# Poti.net
KiCad netlist of a schematic drawn in EAGLE
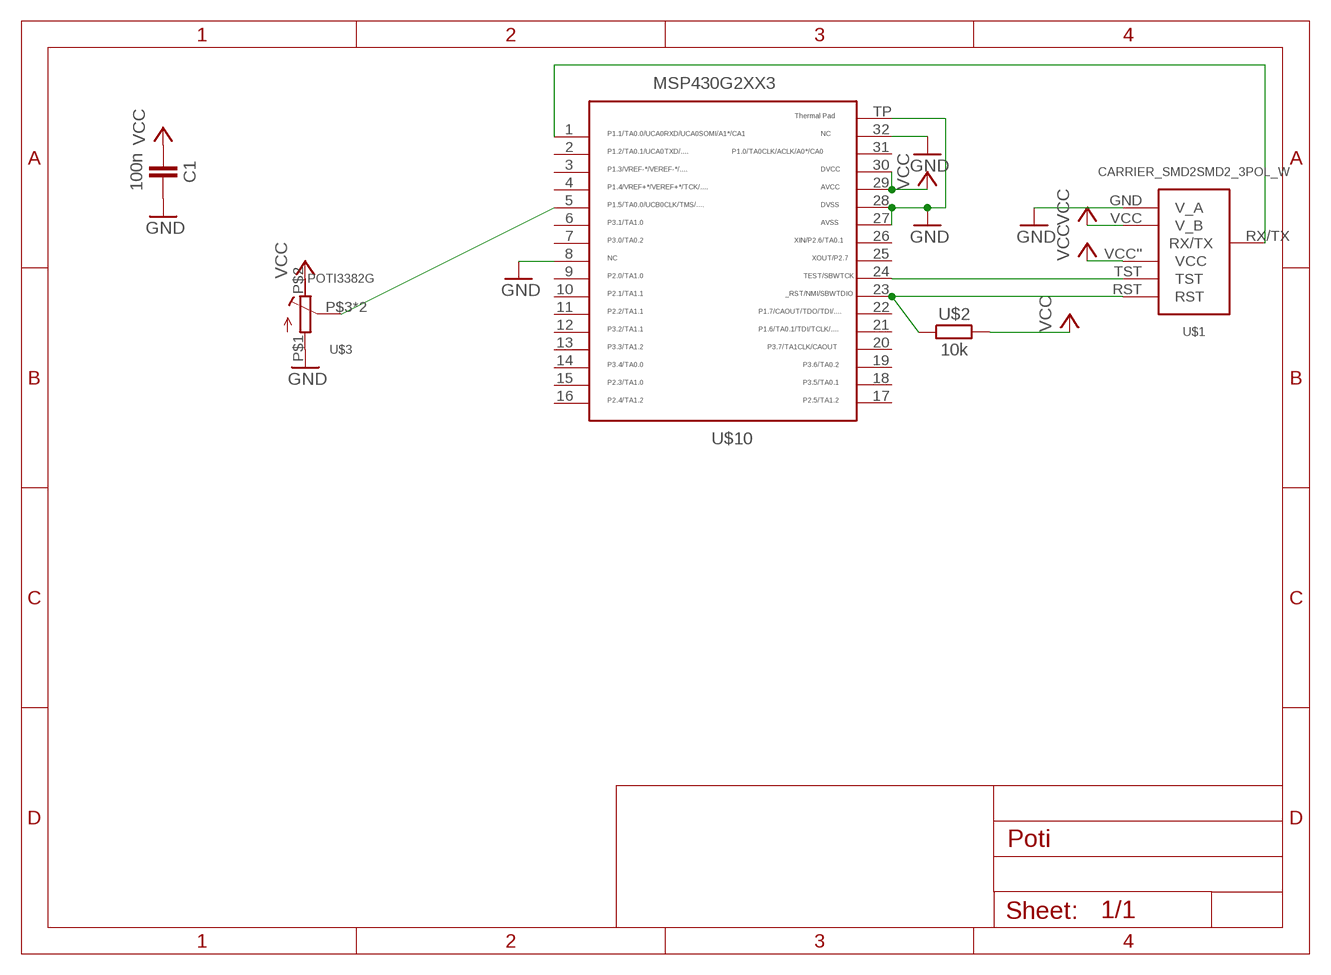
[diagram p0: schematic, sheet 1]

(export (version "E")
  (design (tool "Eeschema 10.0.6"))
  (components
    (comp (ref "C1")
      (value "100n")
      (footprint "eagle-import:603")
      (libsource (lib "eagle-import") (part "CAPACITOR"))
    )
    (comp (ref "U$1")
      (value "CARRIER_SMD2SMD2_3POL_W")
      (footprint "eagle-import:CARRIER_SMD2_WIDE_3POL")
      (libsource (lib "eagle-import") (part "CARRIER_SMD2SMD2_3POL_W"))
    )
    (comp (ref "U$2")
      (value "10k")
      (footprint "eagle-import:603")
      (libsource (lib "eagle-import") (part "RESISTOR0603"))
    )
    (comp (ref "U$3")
      (value "POTI3382G")
      (footprint "eagle-import:3382G")
      (libsource (lib "eagle-import") (part "POTI3382G"))
    )
    (comp (ref "U$10")
      (value "MSP430G2553")
      (footprint "eagle-import:QFN32")
      (libsource (lib "eagle-import") (part "MSP430G2553"))
    )
  )
  (nets
    (net (code "1") (name "GND") (class "Default")
      (node (ref "C1") (pin "2") (pinfunction "2_2") (pintype "passive"))
      (node (ref "U$1") (pin "GND") (pinfunction "V_A_GND") (pintype "bidirectional"))
      (node (ref "U$10") (pin "27") (pinfunction "27_27") (pintype "bidirectional"))
      (node (ref "U$10") (pin "28") (pinfunction "28_28") (pintype "bidirectional"))
      (node (ref "U$10") (pin "32") (pinfunction "32_32") (pintype "bidirectional"))
      (node (ref "U$10") (pin "8") (pinfunction "8_8") (pintype "bidirectional"))
      (node (ref "U$10") (pin "TP") (pinfunction "TP_TP") (pintype "bidirectional"))
      (node (ref "U$3") (pin "P$1") (pinfunction "A_P$1") (pintype "passive"))
    )
    (net (code "2") (name "Net-(U$1-PadRST)") (class "Default")
      (node (ref "U$1") (pin "RST") (pinfunction "RST_RST") (pintype "bidirectional"))
      (node (ref "U$10") (pin "23") (pinfunction "23_23") (pintype "bidirectional"))
      (node (ref "U$2") (pin "1") (pinfunction "1_1") (pintype "passive"))
    )
    (net (code "3") (name "Net-(U$1-PadRX{slash}TX)") (class "Default")
      (node (ref "U$1") (pin "RX/TX") (pinfunction "RX/TX_RX/TX") (pintype "bidirectional"))
      (node (ref "U$10") (pin "1") (pinfunction "1_1") (pintype "bidirectional"))
    )
    (net (code "4") (name "Net-(U$1-PadTST)") (class "Default")
      (node (ref "U$1") (pin "TST") (pinfunction "TST_TST") (pintype "bidirectional"))
      (node (ref "U$10") (pin "24") (pinfunction "24_24") (pintype "bidirectional"))
    )
    (net (code "5") (name "Net-(U$10-Pad5)") (class "Default")
      (node (ref "U$10") (pin "5") (pinfunction "5_5") (pintype "bidirectional"))
      (node (ref "U$3") (pin "P$3") (pinfunction "S_P$3") (pintype "passive"))
      (node (ref "U$3") (pin "P$4") (pinfunction "S_P$4") (pintype "passive"))
    )
    (net (code "6") (name "VCC") (class "Default")
      (node (ref "C1") (pin "1") (pinfunction "1_1") (pintype "passive"))
      (node (ref "U$1") (pin "VCC") (pinfunction "V_B_VCC") (pintype "bidirectional"))
      (node (ref "U$1") (pin "VCC''") (pinfunction "VCC_VCC''") (pintype "bidirectional"))
      (node (ref "U$10") (pin "29") (pinfunction "29_29") (pintype "bidirectional"))
      (node (ref "U$10") (pin "30") (pinfunction "30_30") (pintype "bidirectional"))
      (node (ref "U$2") (pin "2") (pinfunction "2_2") (pintype "passive"))
      (node (ref "U$3") (pin "P$2") (pinfunction "E_P$2") (pintype "passive"))
    )
    (net (code "7") (name "unconnected-(U$10-Pad2)") (class "Default")
      (node (ref "U$10") (pin "2") (pinfunction "2_2") (pintype "bidirectional"))
    )
    (net (code "8") (name "unconnected-(U$10-Pad3)") (class "Default")
      (node (ref "U$10") (pin "3") (pinfunction "3_3") (pintype "bidirectional"))
    )
    (net (code "9") (name "unconnected-(U$10-Pad4)") (class "Default")
      (node (ref "U$10") (pin "4") (pinfunction "4_4") (pintype "bidirectional"))
    )
    (net (code "10") (name "unconnected-(U$10-Pad6)") (class "Default")
      (node (ref "U$10") (pin "6") (pinfunction "6_6") (pintype "bidirectional"))
    )
    (net (code "11") (name "unconnected-(U$10-Pad7)") (class "Default")
      (node (ref "U$10") (pin "7") (pinfunction "7_7") (pintype "bidirectional"))
    )
    (net (code "12") (name "unconnected-(U$10-Pad9)") (class "Default")
      (node (ref "U$10") (pin "9") (pinfunction "9_9") (pintype "bidirectional"))
    )
    (net (code "13") (name "unconnected-(U$10-Pad10)") (class "Default")
      (node (ref "U$10") (pin "10") (pinfunction "10_10") (pintype "bidirectional"))
    )
    (net (code "14") (name "unconnected-(U$10-Pad11)") (class "Default")
      (node (ref "U$10") (pin "11") (pinfunction "11_11") (pintype "bidirectional"))
    )
    (net (code "15") (name "unconnected-(U$10-Pad12)") (class "Default")
      (node (ref "U$10") (pin "12") (pinfunction "12_12") (pintype "bidirectional"))
    )
    (net (code "16") (name "unconnected-(U$10-Pad13)") (class "Default")
      (node (ref "U$10") (pin "13") (pinfunction "13_13") (pintype "bidirectional"))
    )
    (net (code "17") (name "unconnected-(U$10-Pad14)") (class "Default")
      (node (ref "U$10") (pin "14") (pinfunction "14_14") (pintype "bidirectional"))
    )
    (net (code "18") (name "unconnected-(U$10-Pad15)") (class "Default")
      (node (ref "U$10") (pin "15") (pinfunction "15_15") (pintype "bidirectional"))
    )
    (net (code "19") (name "unconnected-(U$10-Pad16)") (class "Default")
      (node (ref "U$10") (pin "16") (pinfunction "16_16") (pintype "bidirectional"))
    )
    (net (code "20") (name "unconnected-(U$10-Pad17)") (class "Default")
      (node (ref "U$10") (pin "17") (pinfunction "17_17") (pintype "bidirectional"))
    )
    (net (code "21") (name "unconnected-(U$10-Pad18)") (class "Default")
      (node (ref "U$10") (pin "18") (pinfunction "18_18") (pintype "bidirectional"))
    )
    (net (code "22") (name "unconnected-(U$10-Pad19)") (class "Default")
      (node (ref "U$10") (pin "19") (pinfunction "19_19") (pintype "bidirectional"))
    )
    (net (code "23") (name "unconnected-(U$10-Pad20)") (class "Default")
      (node (ref "U$10") (pin "20") (pinfunction "20_20") (pintype "bidirectional"))
    )
    (net (code "24") (name "unconnected-(U$10-Pad21)") (class "Default")
      (node (ref "U$10") (pin "21") (pinfunction "21_21") (pintype "bidirectional"))
    )
    (net (code "25") (name "unconnected-(U$10-Pad22)") (class "Default")
      (node (ref "U$10") (pin "22") (pinfunction "22_22") (pintype "bidirectional"))
    )
    (net (code "26") (name "unconnected-(U$10-Pad25)") (class "Default")
      (node (ref "U$10") (pin "25") (pinfunction "25_25") (pintype "bidirectional"))
    )
    (net (code "27") (name "unconnected-(U$10-Pad26)") (class "Default")
      (node (ref "U$10") (pin "26") (pinfunction "26_26") (pintype "bidirectional"))
    )
    (net (code "28") (name "unconnected-(U$10-Pad31)") (class "Default")
      (node (ref "U$10") (pin "31") (pinfunction "31_31") (pintype "bidirectional"))
    )
  )
)
